# Teensy2ESP8266.net
KiCad netlist of a schematic drawn in EAGLE
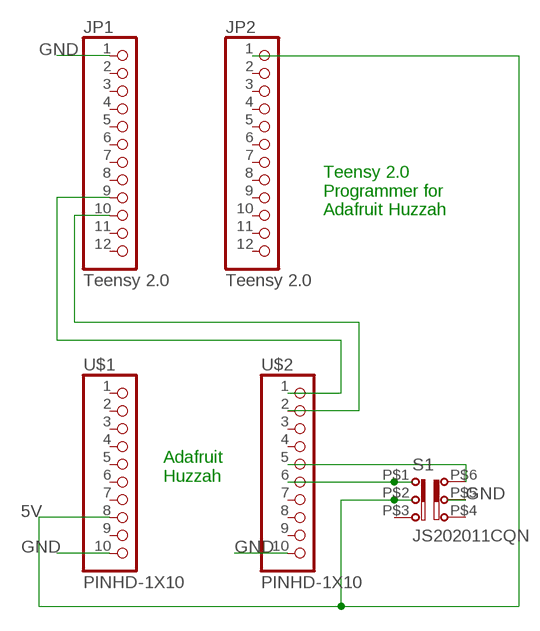
[diagram p0: schematic, sheet 1]

(export (version "E")
  (design (tool "Eeschema 10.0.6"))
  (components
    (comp (ref "JP1")
      (value "Teensy 2.0")
      (footprint "eagle-import:1X12")
      (libsource (lib "eagle-import") (part "PINHD-1X12"))
    )
    (comp (ref "JP2")
      (value "Teensy 2.0")
      (footprint "eagle-import:1X12")
      (libsource (lib "eagle-import") (part "PINHD-1X12"))
    )
    (comp (ref "S1")
      (value "JS202011CQN")
      (footprint "eagle-import:JS202011CQN")
      (libsource (lib "eagle-import") (part "JS202011CQN"))
    )
    (comp (ref "U$1")
      (value "PINHD-1X10")
      (footprint "eagle-import:1X10-BIG")
      (libsource (lib "eagle-import") (part "PINHD-1X10"))
    )
    (comp (ref "U$2")
      (value "PINHD-1X10")
      (footprint "eagle-import:1X10-BIG")
      (libsource (lib "eagle-import") (part "PINHD-1X10"))
    )
  )
  (nets
    (net (code "1") (name "/5V") (class "Default")
      (node (ref "JP2") (pin "1") (pinfunction "1_1") (pintype "passive"))
      (node (ref "S1") (pin "P$2") (pinfunction "2_P$2") (pintype "passive"))
      (node (ref "U$1") (pin "8") (pinfunction "8_8") (pintype "passive"))
    )
    (net (code "2") (name "/GND") (class "Default")
      (node (ref "JP1") (pin "1") (pinfunction "1_1") (pintype "passive"))
      (node (ref "S1") (pin "P$5") (pinfunction "5_P$5") (pintype "passive"))
      (node (ref "U$1") (pin "10") (pinfunction "10_10") (pintype "passive"))
      (node (ref "U$2") (pin "10") (pinfunction "10_10") (pintype "passive"))
    )
    (net (code "3") (name "Net-(JP1-Pad9)") (class "Default")
      (node (ref "JP1") (pin "9") (pinfunction "9_9") (pintype "passive"))
      (node (ref "U$2") (pin "1") (pinfunction "1_1") (pintype "passive"))
    )
    (net (code "4") (name "Net-(JP1-Pad10)") (class "Default")
      (node (ref "JP1") (pin "10") (pinfunction "10_10") (pintype "passive"))
      (node (ref "U$2") (pin "2") (pinfunction "2_2") (pintype "passive"))
    )
    (net (code "5") (name "Net-(S1-1)") (class "Default")
      (node (ref "S1") (pin "P$1") (pinfunction "1_P$1") (pintype "passive"))
      (node (ref "U$2") (pin "6") (pinfunction "6_6") (pintype "passive"))
    )
    (net (code "6") (name "Net-(S1-4)") (class "Default")
      (node (ref "S1") (pin "P$6") (pinfunction "4_P$6") (pintype "passive"))
      (node (ref "U$2") (pin "5") (pinfunction "5_5") (pintype "passive"))
    )
    (net (code "7") (name "unconnected-(JP1-Pad2)") (class "Default")
      (node (ref "JP1") (pin "2") (pinfunction "2_2") (pintype "passive"))
    )
    (net (code "8") (name "unconnected-(JP1-Pad3)") (class "Default")
      (node (ref "JP1") (pin "3") (pinfunction "3_3") (pintype "passive"))
    )
    (net (code "9") (name "unconnected-(JP1-Pad4)") (class "Default")
      (node (ref "JP1") (pin "4") (pinfunction "4_4") (pintype "passive"))
    )
    (net (code "10") (name "unconnected-(JP1-Pad5)") (class "Default")
      (node (ref "JP1") (pin "5") (pinfunction "5_5") (pintype "passive"))
    )
    (net (code "11") (name "unconnected-(JP1-Pad6)") (class "Default")
      (node (ref "JP1") (pin "6") (pinfunction "6_6") (pintype "passive"))
    )
    (net (code "12") (name "unconnected-(JP1-Pad7)") (class "Default")
      (node (ref "JP1") (pin "7") (pinfunction "7_7") (pintype "passive"))
    )
    (net (code "13") (name "unconnected-(JP1-Pad8)") (class "Default")
      (node (ref "JP1") (pin "8") (pinfunction "8_8") (pintype "passive"))
    )
    (net (code "14") (name "unconnected-(JP1-Pad11)") (class "Default")
      (node (ref "JP1") (pin "11") (pinfunction "11_11") (pintype "passive"))
    )
    (net (code "15") (name "unconnected-(JP1-Pad12)") (class "Default")
      (node (ref "JP1") (pin "12") (pinfunction "12_12") (pintype "passive"))
    )
    (net (code "16") (name "unconnected-(JP2-Pad2)") (class "Default")
      (node (ref "JP2") (pin "2") (pinfunction "2_2") (pintype "passive"))
    )
    (net (code "17") (name "unconnected-(JP2-Pad3)") (class "Default")
      (node (ref "JP2") (pin "3") (pinfunction "3_3") (pintype "passive"))
    )
    (net (code "18") (name "unconnected-(JP2-Pad4)") (class "Default")
      (node (ref "JP2") (pin "4") (pinfunction "4_4") (pintype "passive"))
    )
    (net (code "19") (name "unconnected-(JP2-Pad5)") (class "Default")
      (node (ref "JP2") (pin "5") (pinfunction "5_5") (pintype "passive"))
    )
    (net (code "20") (name "unconnected-(JP2-Pad6)") (class "Default")
      (node (ref "JP2") (pin "6") (pinfunction "6_6") (pintype "passive"))
    )
    (net (code "21") (name "unconnected-(JP2-Pad7)") (class "Default")
      (node (ref "JP2") (pin "7") (pinfunction "7_7") (pintype "passive"))
    )
    (net (code "22") (name "unconnected-(JP2-Pad8)") (class "Default")
      (node (ref "JP2") (pin "8") (pinfunction "8_8") (pintype "passive"))
    )
    (net (code "23") (name "unconnected-(JP2-Pad9)") (class "Default")
      (node (ref "JP2") (pin "9") (pinfunction "9_9") (pintype "passive"))
    )
    (net (code "24") (name "unconnected-(JP2-Pad10)") (class "Default")
      (node (ref "JP2") (pin "10") (pinfunction "10_10") (pintype "passive"))
    )
    (net (code "25") (name "unconnected-(JP2-Pad11)") (class "Default")
      (node (ref "JP2") (pin "11") (pinfunction "11_11") (pintype "passive"))
    )
    (net (code "26") (name "unconnected-(JP2-Pad12)") (class "Default")
      (node (ref "JP2") (pin "12") (pinfunction "12_12") (pintype "passive"))
    )
    (net (code "27") (name "unconnected-(S1-3-PadP$3)") (class "Default")
      (node (ref "S1") (pin "P$3") (pinfunction "3_P$3") (pintype "passive"))
    )
    (net (code "28") (name "unconnected-(S1-6-PadP$4)") (class "Default")
      (node (ref "S1") (pin "P$4") (pinfunction "6_P$4") (pintype "passive"))
    )
    (net (code "29") (name "unconnected-(U$1-Pad1)") (class "Default")
      (node (ref "U$1") (pin "1") (pinfunction "1_1") (pintype "passive"))
    )
    (net (code "30") (name "unconnected-(U$1-Pad2)") (class "Default")
      (node (ref "U$1") (pin "2") (pinfunction "2_2") (pintype "passive"))
    )
    (net (code "31") (name "unconnected-(U$1-Pad3)") (class "Default")
      (node (ref "U$1") (pin "3") (pinfunction "3_3") (pintype "passive"))
    )
    (net (code "32") (name "unconnected-(U$1-Pad4)") (class "Default")
      (node (ref "U$1") (pin "4") (pinfunction "4_4") (pintype "passive"))
    )
    (net (code "33") (name "unconnected-(U$1-Pad5)") (class "Default")
      (node (ref "U$1") (pin "5") (pinfunction "5_5") (pintype "passive"))
    )
    (net (code "34") (name "unconnected-(U$1-Pad6)") (class "Default")
      (node (ref "U$1") (pin "6") (pinfunction "6_6") (pintype "passive"))
    )
    (net (code "35") (name "unconnected-(U$1-Pad7)") (class "Default")
      (node (ref "U$1") (pin "7") (pinfunction "7_7") (pintype "passive"))
    )
    (net (code "36") (name "unconnected-(U$1-Pad9)") (class "Default")
      (node (ref "U$1") (pin "9") (pinfunction "9_9") (pintype "passive"))
    )
    (net (code "37") (name "unconnected-(U$2-Pad3)") (class "Default")
      (node (ref "U$2") (pin "3") (pinfunction "3_3") (pintype "passive"))
    )
    (net (code "38") (name "unconnected-(U$2-Pad4)") (class "Default")
      (node (ref "U$2") (pin "4") (pinfunction "4_4") (pintype "passive"))
    )
    (net (code "39") (name "unconnected-(U$2-Pad7)") (class "Default")
      (node (ref "U$2") (pin "7") (pinfunction "7_7") (pintype "passive"))
    )
    (net (code "40") (name "unconnected-(U$2-Pad8)") (class "Default")
      (node (ref "U$2") (pin "8") (pinfunction "8_8") (pintype "passive"))
    )
    (net (code "41") (name "unconnected-(U$2-Pad9)") (class "Default")
      (node (ref "U$2") (pin "9") (pinfunction "9_9") (pintype "passive"))
    )
  )
)
